# Power.net
KiCad netlist of a schematic drawn in EAGLE
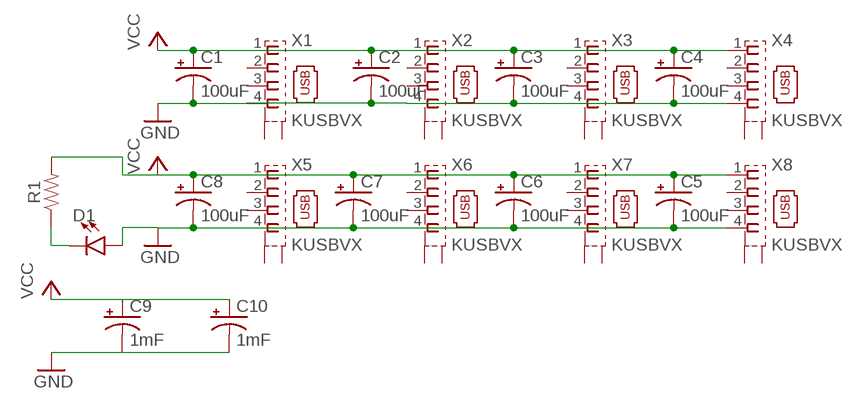
[diagram p0: schematic, sheet 1]

(export (version "E")
  (design (tool "Eeschema 10.0.6"))
  (components
    (comp (ref "C1")
      (value "100uF")
      (footprint "eagle-import:CPOL-RADIAL-2.5MM-6.5MM")
      (libsource (lib "eagle-import") (part "100UF-POLAR-RADIAL-2.5MM-25V-20%"))
    )
    (comp (ref "C2")
      (value "100uF")
      (footprint "eagle-import:CPOL-RADIAL-2.5MM-6.5MM")
      (libsource (lib "eagle-import") (part "100UF-POLAR-RADIAL-2.5MM-25V-20%"))
    )
    (comp (ref "C3")
      (value "100uF")
      (footprint "eagle-import:CPOL-RADIAL-2.5MM-6.5MM")
      (libsource (lib "eagle-import") (part "100UF-POLAR-RADIAL-2.5MM-25V-20%"))
    )
    (comp (ref "C4")
      (value "100uF")
      (footprint "eagle-import:CPOL-RADIAL-2.5MM-6.5MM")
      (libsource (lib "eagle-import") (part "100UF-POLAR-RADIAL-2.5MM-25V-20%"))
    )
    (comp (ref "C5")
      (value "100uF")
      (footprint "eagle-import:CPOL-RADIAL-2.5MM-6.5MM")
      (libsource (lib "eagle-import") (part "100UF-POLAR-RADIAL-2.5MM-25V-20%"))
    )
    (comp (ref "C6")
      (value "100uF")
      (footprint "eagle-import:CPOL-RADIAL-2.5MM-6.5MM")
      (libsource (lib "eagle-import") (part "100UF-POLAR-RADIAL-2.5MM-25V-20%"))
    )
    (comp (ref "C7")
      (value "100uF")
      (footprint "eagle-import:CPOL-RADIAL-2.5MM-6.5MM")
      (libsource (lib "eagle-import") (part "100UF-POLAR-RADIAL-2.5MM-25V-20%"))
    )
    (comp (ref "C8")
      (value "100uF")
      (footprint "eagle-import:CPOL-RADIAL-2.5MM-6.5MM")
      (libsource (lib "eagle-import") (part "100UF-POLAR-RADIAL-2.5MM-25V-20%"))
    )
    (comp (ref "C9")
      (value "1mF")
      (footprint "eagle-import:CPOL-RADIAL-5MM-10MM")
      (libsource (lib "eagle-import") (part "1000UF-RADIAL-5MM-25V-20%"))
    )
    (comp (ref "C10")
      (value "1mF")
      (footprint "eagle-import:CPOL-RADIAL-5MM-10MM")
      (libsource (lib "eagle-import") (part "1000UF-RADIAL-5MM-25V-20%"))
    )
    (comp (ref "D1")
      (value "LED3MM")
      (footprint "eagle-import:LED_3MM")
      (libsource (lib "eagle-import") (part "LED3MM"))
    )
    (comp (ref "R1")
      (value "RESISTORAXIAL-0.3")
      (footprint "eagle-import:AXIAL-0.3")
      (libsource (lib "eagle-import") (part "RESISTORAXIAL-0.3"))
    )
    (comp (ref "X1")
      (value "KUSBVX")
      (footprint "eagle-import:KUSBVX")
      (libsource (lib "eagle-import") (part "KUSBVX"))
    )
    (comp (ref "X2")
      (value "KUSBVX")
      (footprint "eagle-import:KUSBVX")
      (libsource (lib "eagle-import") (part "KUSBVX"))
    )
    (comp (ref "X3")
      (value "KUSBVX")
      (footprint "eagle-import:KUSBVX")
      (libsource (lib "eagle-import") (part "KUSBVX"))
    )
    (comp (ref "X4")
      (value "KUSBVX")
      (footprint "eagle-import:KUSBVX")
      (libsource (lib "eagle-import") (part "KUSBVX"))
    )
    (comp (ref "X5")
      (value "KUSBVX")
      (footprint "eagle-import:KUSBVX")
      (libsource (lib "eagle-import") (part "KUSBVX"))
    )
    (comp (ref "X6")
      (value "KUSBVX")
      (footprint "eagle-import:KUSBVX")
      (libsource (lib "eagle-import") (part "KUSBVX"))
    )
    (comp (ref "X7")
      (value "KUSBVX")
      (footprint "eagle-import:KUSBVX")
      (libsource (lib "eagle-import") (part "KUSBVX"))
    )
    (comp (ref "X8")
      (value "KUSBVX")
      (footprint "eagle-import:KUSBVX")
      (libsource (lib "eagle-import") (part "KUSBVX"))
    )
  )
  (nets
    (net (code "1") (name "GND") (class "Default")
      (node (ref "C1") (pin "2") (pinfunction "-_2") (pintype "passive"))
      (node (ref "C10") (pin "-") (pinfunction "-_-") (pintype "passive"))
      (node (ref "C2") (pin "2") (pinfunction "-_2") (pintype "passive"))
      (node (ref "C3") (pin "2") (pinfunction "-_2") (pintype "passive"))
      (node (ref "C4") (pin "2") (pinfunction "-_2") (pintype "passive"))
      (node (ref "C5") (pin "2") (pinfunction "-_2") (pintype "passive"))
      (node (ref "C6") (pin "2") (pinfunction "-_2") (pintype "passive"))
      (node (ref "C7") (pin "2") (pinfunction "-_2") (pintype "passive"))
      (node (ref "C8") (pin "2") (pinfunction "-_2") (pintype "passive"))
      (node (ref "C9") (pin "-") (pinfunction "-_-") (pintype "passive"))
      (node (ref "D1") (pin "A") (pinfunction "A_A") (pintype "passive"))
      (node (ref "X1") (pin "4") (pinfunction "4_4") (pintype "passive"))
      (node (ref "X2") (pin "4") (pinfunction "4_4") (pintype "passive"))
      (node (ref "X3") (pin "4") (pinfunction "4_4") (pintype "passive"))
      (node (ref "X4") (pin "4") (pinfunction "4_4") (pintype "passive"))
      (node (ref "X5") (pin "4") (pinfunction "4_4") (pintype "passive"))
      (node (ref "X6") (pin "4") (pinfunction "4_4") (pintype "passive"))
      (node (ref "X7") (pin "4") (pinfunction "4_4") (pintype "passive"))
      (node (ref "X8") (pin "4") (pinfunction "4_4") (pintype "passive"))
    )
    (net (code "2") (name "Net-(D1-C)") (class "Default")
      (node (ref "D1") (pin "K") (pinfunction "C_K") (pintype "passive"))
      (node (ref "R1") (pin "P$1") (pinfunction "1_P$1") (pintype "passive"))
    )
    (net (code "3") (name "VCC") (class "Default")
      (node (ref "C1") (pin "1") (pinfunction "+_1") (pintype "passive"))
      (node (ref "C10") (pin "+") (pinfunction "+_+") (pintype "passive"))
      (node (ref "C2") (pin "1") (pinfunction "+_1") (pintype "passive"))
      (node (ref "C3") (pin "1") (pinfunction "+_1") (pintype "passive"))
      (node (ref "C4") (pin "1") (pinfunction "+_1") (pintype "passive"))
      (node (ref "C5") (pin "1") (pinfunction "+_1") (pintype "passive"))
      (node (ref "C6") (pin "1") (pinfunction "+_1") (pintype "passive"))
      (node (ref "C7") (pin "1") (pinfunction "+_1") (pintype "passive"))
      (node (ref "C8") (pin "1") (pinfunction "+_1") (pintype "passive"))
      (node (ref "C9") (pin "+") (pinfunction "+_+") (pintype "passive"))
      (node (ref "R1") (pin "P$2") (pinfunction "2_P$2") (pintype "passive"))
      (node (ref "X1") (pin "1") (pinfunction "1_1") (pintype "passive"))
      (node (ref "X2") (pin "1") (pinfunction "1_1") (pintype "passive"))
      (node (ref "X3") (pin "1") (pinfunction "1_1") (pintype "passive"))
      (node (ref "X4") (pin "1") (pinfunction "1_1") (pintype "passive"))
      (node (ref "X5") (pin "1") (pinfunction "1_1") (pintype "passive"))
      (node (ref "X6") (pin "1") (pinfunction "1_1") (pintype "passive"))
      (node (ref "X7") (pin "1") (pinfunction "1_1") (pintype "passive"))
      (node (ref "X8") (pin "1") (pinfunction "1_1") (pintype "passive"))
    )
    (net (code "4") (name "unconnected-(X1-Pad2)") (class "Default")
      (node (ref "X1") (pin "2") (pinfunction "2_2") (pintype "passive"))
    )
    (net (code "5") (name "unconnected-(X1-Pad3)") (class "Default")
      (node (ref "X1") (pin "3") (pinfunction "3_3") (pintype "passive"))
    )
    (net (code "6") (name "unconnected-(X1-S1-PadM1)") (class "Default")
      (node (ref "X1") (pin "M1") (pinfunction "S1_M1") (pintype "passive"))
    )
    (net (code "7") (name "unconnected-(X1-S2-PadM2)") (class "Default")
      (node (ref "X1") (pin "M2") (pinfunction "S2_M2") (pintype "passive"))
    )
    (net (code "8") (name "unconnected-(X2-Pad2)") (class "Default")
      (node (ref "X2") (pin "2") (pinfunction "2_2") (pintype "passive"))
    )
    (net (code "9") (name "unconnected-(X2-Pad3)") (class "Default")
      (node (ref "X2") (pin "3") (pinfunction "3_3") (pintype "passive"))
    )
    (net (code "10") (name "unconnected-(X2-S1-PadM1)") (class "Default")
      (node (ref "X2") (pin "M1") (pinfunction "S1_M1") (pintype "passive"))
    )
    (net (code "11") (name "unconnected-(X2-S2-PadM2)") (class "Default")
      (node (ref "X2") (pin "M2") (pinfunction "S2_M2") (pintype "passive"))
    )
    (net (code "12") (name "unconnected-(X3-Pad2)") (class "Default")
      (node (ref "X3") (pin "2") (pinfunction "2_2") (pintype "passive"))
    )
    (net (code "13") (name "unconnected-(X3-Pad3)") (class "Default")
      (node (ref "X3") (pin "3") (pinfunction "3_3") (pintype "passive"))
    )
    (net (code "14") (name "unconnected-(X3-S1-PadM1)") (class "Default")
      (node (ref "X3") (pin "M1") (pinfunction "S1_M1") (pintype "passive"))
    )
    (net (code "15") (name "unconnected-(X3-S2-PadM2)") (class "Default")
      (node (ref "X3") (pin "M2") (pinfunction "S2_M2") (pintype "passive"))
    )
    (net (code "16") (name "unconnected-(X4-Pad2)") (class "Default")
      (node (ref "X4") (pin "2") (pinfunction "2_2") (pintype "passive"))
    )
    (net (code "17") (name "unconnected-(X4-Pad3)") (class "Default")
      (node (ref "X4") (pin "3") (pinfunction "3_3") (pintype "passive"))
    )
    (net (code "18") (name "unconnected-(X4-S1-PadM1)") (class "Default")
      (node (ref "X4") (pin "M1") (pinfunction "S1_M1") (pintype "passive"))
    )
    (net (code "19") (name "unconnected-(X4-S2-PadM2)") (class "Default")
      (node (ref "X4") (pin "M2") (pinfunction "S2_M2") (pintype "passive"))
    )
    (net (code "20") (name "unconnected-(X5-Pad2)") (class "Default")
      (node (ref "X5") (pin "2") (pinfunction "2_2") (pintype "passive"))
    )
    (net (code "21") (name "unconnected-(X5-Pad3)") (class "Default")
      (node (ref "X5") (pin "3") (pinfunction "3_3") (pintype "passive"))
    )
    (net (code "22") (name "unconnected-(X5-S1-PadM1)") (class "Default")
      (node (ref "X5") (pin "M1") (pinfunction "S1_M1") (pintype "passive"))
    )
    (net (code "23") (name "unconnected-(X5-S2-PadM2)") (class "Default")
      (node (ref "X5") (pin "M2") (pinfunction "S2_M2") (pintype "passive"))
    )
    (net (code "24") (name "unconnected-(X6-Pad2)") (class "Default")
      (node (ref "X6") (pin "2") (pinfunction "2_2") (pintype "passive"))
    )
    (net (code "25") (name "unconnected-(X6-Pad3)") (class "Default")
      (node (ref "X6") (pin "3") (pinfunction "3_3") (pintype "passive"))
    )
    (net (code "26") (name "unconnected-(X6-S1-PadM1)") (class "Default")
      (node (ref "X6") (pin "M1") (pinfunction "S1_M1") (pintype "passive"))
    )
    (net (code "27") (name "unconnected-(X6-S2-PadM2)") (class "Default")
      (node (ref "X6") (pin "M2") (pinfunction "S2_M2") (pintype "passive"))
    )
    (net (code "28") (name "unconnected-(X7-Pad2)") (class "Default")
      (node (ref "X7") (pin "2") (pinfunction "2_2") (pintype "passive"))
    )
    (net (code "29") (name "unconnected-(X7-Pad3)") (class "Default")
      (node (ref "X7") (pin "3") (pinfunction "3_3") (pintype "passive"))
    )
    (net (code "30") (name "unconnected-(X7-S1-PadM1)") (class "Default")
      (node (ref "X7") (pin "M1") (pinfunction "S1_M1") (pintype "passive"))
    )
    (net (code "31") (name "unconnected-(X7-S2-PadM2)") (class "Default")
      (node (ref "X7") (pin "M2") (pinfunction "S2_M2") (pintype "passive"))
    )
    (net (code "32") (name "unconnected-(X8-Pad2)") (class "Default")
      (node (ref "X8") (pin "2") (pinfunction "2_2") (pintype "passive"))
    )
    (net (code "33") (name "unconnected-(X8-Pad3)") (class "Default")
      (node (ref "X8") (pin "3") (pinfunction "3_3") (pintype "passive"))
    )
    (net (code "34") (name "unconnected-(X8-S1-PadM1)") (class "Default")
      (node (ref "X8") (pin "M1") (pinfunction "S1_M1") (pintype "passive"))
    )
    (net (code "35") (name "unconnected-(X8-S2-PadM2)") (class "Default")
      (node (ref "X8") (pin "M2") (pinfunction "S2_M2") (pintype "passive"))
    )
  )
)
